# KursSCH2.net
KiCad netlist of a schematic drawn in Altium Designer
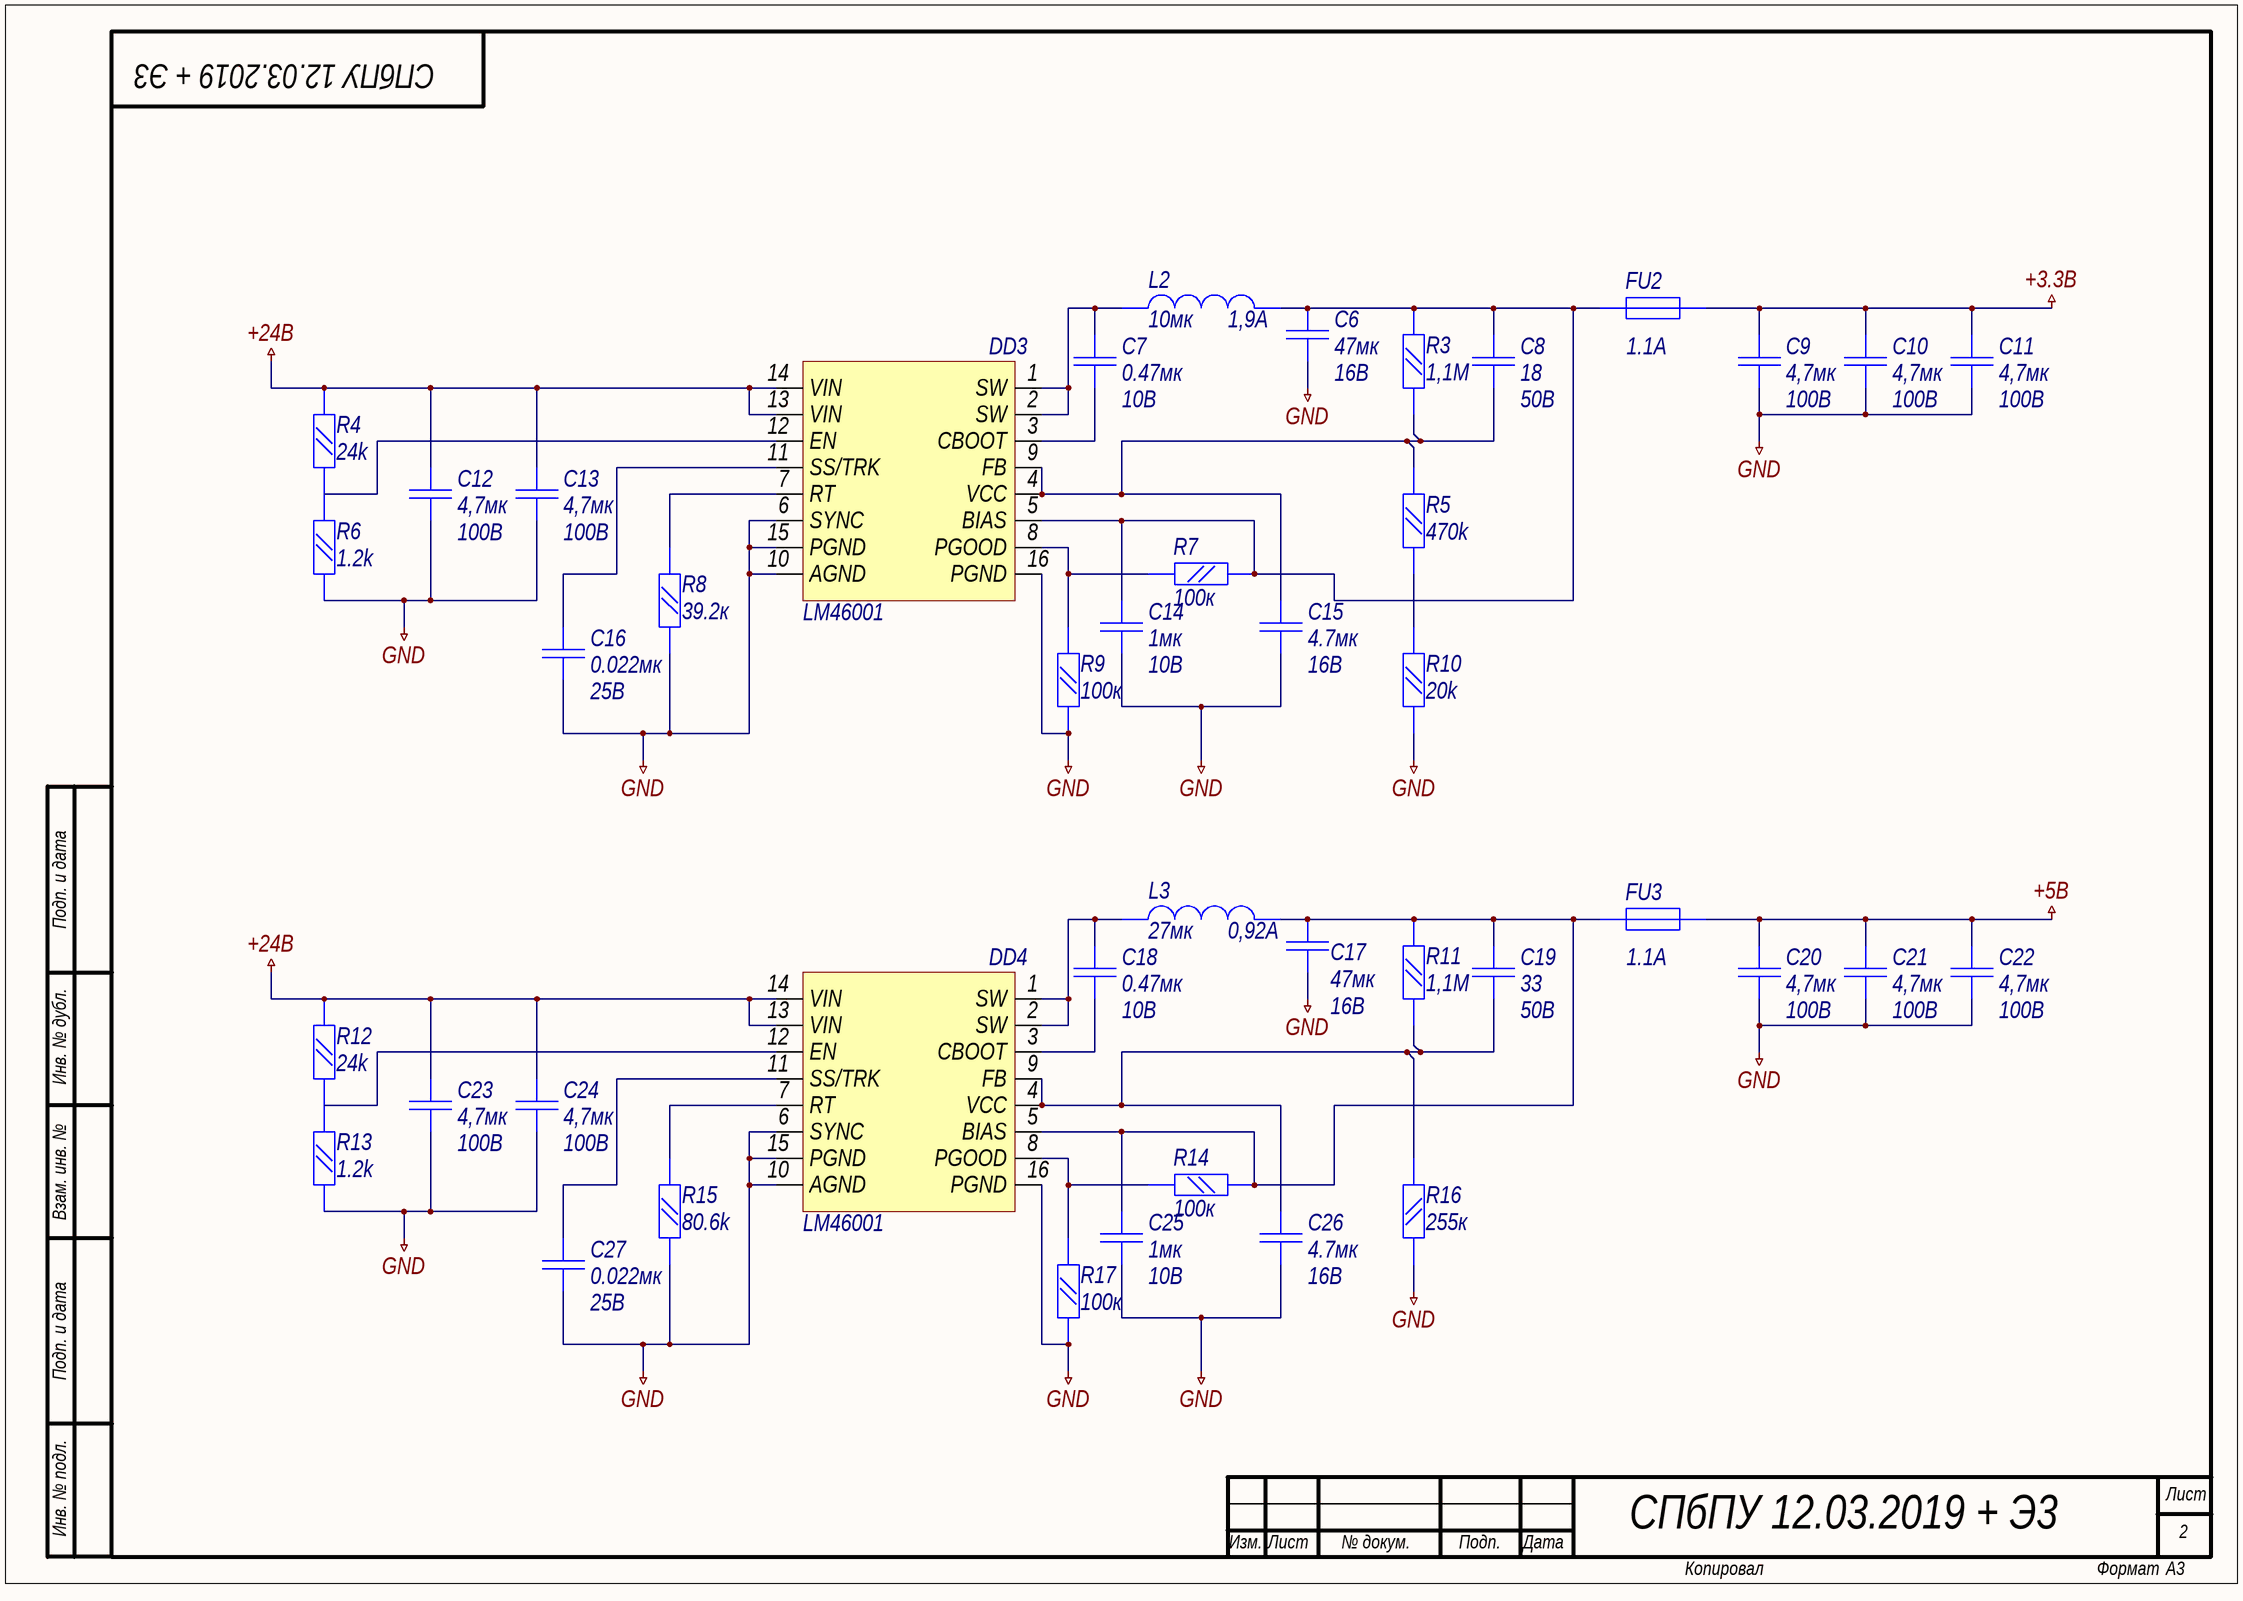
[diagram p0: KursSCH2.schdoc]

(export (version "E")
  (design (tool "Eeschema 10.0.6"))
  (components
    (comp (ref "C6")
      (value "47мк")
      (footprint "C1210")
      (fields
        (field (name "VOLTAGE") "16В")
        (field (name "PART NUMBER") "GRM32ER61C476KE15L")
        (field (name "TOLERANCE") "±10%")
        (field (name "MANUFACTURER") "Murata")
      )
      (libsource (lib "Lib_IMP_GOST") (part "Capacitor"))
    )
    (comp (ref "C7")
      (value "0.47мк")
      (footprint "C0603")
      (fields
        (field (name "VOLTAGE") "10В")
        (field (name "PART NUMBER") "GRM188R71A474KA61D")
        (field (name "TOLERANCE") "±10%")
        (field (name "MANUFACTURER") "Murata")
      )
      (libsource (lib "Lib_IMP_GOST") (part "Capacitor"))
    )
    (comp (ref "C8")
      (value "18")
      (footprint "C0402")
      (fields
        (field (name "VOLTAGE") "50В")
        (field (name "PART NUMBER") "GRM1555C1H180JA01D")
        (field (name "TOLERANCE") "±5%")
        (field (name "MANUFACTURER") "Murata")
      )
      (libsource (lib "Lib_IMP_GOST") (part "Capacitor"))
    )
    (comp (ref "C9")
      (value "4,7мк")
      (footprint "C1206")
      (fields
        (field (name "VOLTAGE") "100В")
        (field (name "PART NUMBER") "GRM31CC72A475ME11")
        (field (name "TOLERANCE") "±10%")
        (field (name "MANUFACTURER") "Murata")
      )
      (libsource (lib "Lib_IMP_GOST") (part "Capacitor"))
    )
    (comp (ref "C10")
      (value "4,7мк")
      (footprint "C1206")
      (fields
        (field (name "VOLTAGE") "100В")
        (field (name "PART NUMBER") "GRM31CC72A475ME11")
        (field (name "TOLERANCE") "±10%")
        (field (name "MANUFACTURER") "Murata")
      )
      (libsource (lib "Lib_IMP_GOST") (part "Capacitor"))
    )
    (comp (ref "C11")
      (value "4,7мк")
      (footprint "C1206")
      (fields
        (field (name "VOLTAGE") "100В")
        (field (name "PART NUMBER") "GRM31CC72A475ME11")
        (field (name "TOLERANCE") "±10%")
        (field (name "MANUFACTURER") "Murata")
      )
      (libsource (lib "Lib_IMP_GOST") (part "Capacitor"))
    )
    (comp (ref "C12")
      (value "4,7мк")
      (footprint "C1206")
      (fields
        (field (name "VOLTAGE") "100В")
        (field (name "PART NUMBER") "GRM31CC72A475ME11")
        (field (name "TOLERANCE") "±10%")
        (field (name "MANUFACTURER") "Murata")
      )
      (libsource (lib "Lib_IMP_GOST") (part "Capacitor"))
    )
    (comp (ref "C13")
      (value "4,7мк")
      (footprint "C1206")
      (fields
        (field (name "VOLTAGE") "100В")
        (field (name "PART NUMBER") "GRM31CC72A475ME11")
        (field (name "TOLERANCE") "±10%")
        (field (name "MANUFACTURER") "Murata")
      )
      (libsource (lib "Lib_IMP_GOST") (part "Capacitor"))
    )
    (comp (ref "C14")
      (value "1мк")
      (footprint "C0603")
      (fields
        (field (name "VOLTAGE") "10В")
        (field (name "PART NUMBER") "GRM188R61A105KA01D")
        (field (name "TOLERANCE") "±10%")
        (field (name "MANUFACTURER") "Murata")
      )
      (libsource (lib "Lib_IMP_GOST") (part "Capacitor"))
    )
    (comp (ref "C15")
      (value "4.7мк")
      (footprint "C0603")
      (fields
        (field (name "VOLTAGE") "16В")
        (field (name "PART NUMBER") "GRM188R61A475KE15D")
        (field (name "TOLERANCE") "±10%")
        (field (name "MANUFACTURER") "Murata")
      )
      (libsource (lib "Lib_IMP_GOST") (part "Capacitor"))
    )
    (comp (ref "C16")
      (value "0.022мк")
      (footprint "C0603")
      (fields
        (field (name "VOLTAGE") "25В")
        (field (name "PART NUMBER") "GRM188R71E223JA01D")
        (field (name "TOLERANCE") "±5%")
        (field (name "MANUFACTURER") "Murata")
      )
      (libsource (lib "Lib_IMP_GOST") (part "Capacitor"))
    )
    (comp (ref "C17")
      (value "47мк")
      (footprint "C1210")
      (fields
        (field (name "VOLTAGE") "16В")
        (field (name "PART NUMBER") "GRM32ER61C476KE15L")
        (field (name "TOLERANCE") "±10%")
        (field (name "MANUFACTURER") "Murata")
      )
      (libsource (lib "Lib_IMP_GOST") (part "Capacitor"))
    )
    (comp (ref "C18")
      (value "0.47мк")
      (footprint "C0603")
      (fields
        (field (name "VOLTAGE") "10В")
        (field (name "PART NUMBER") "GRM188R71A474KA61D")
        (field (name "TOLERANCE") "±10%")
        (field (name "MANUFACTURER") "Murata")
      )
      (libsource (lib "Lib_IMP_GOST") (part "Capacitor"))
    )
    (comp (ref "C19")
      (value "33")
      (footprint "C0402")
      (fields
        (field (name "VOLTAGE") "50В")
        (field (name "PART NUMBER") "GRM1555C1H330JA01D")
        (field (name "TOLERANCE") "±5%")
        (field (name "MANUFACTURER") "Murata")
      )
      (libsource (lib "Lib_IMP_GOST") (part "Capacitor"))
    )
    (comp (ref "C20")
      (value "4,7мк")
      (footprint "C1206")
      (fields
        (field (name "VOLTAGE") "100В")
        (field (name "PART NUMBER") "GRM31CC72A475ME11")
        (field (name "TOLERANCE") "±10%")
        (field (name "MANUFACTURER") "Murata")
      )
      (libsource (lib "Lib_IMP_GOST") (part "Capacitor"))
    )
    (comp (ref "C21")
      (value "4,7мк")
      (footprint "C1206")
      (fields
        (field (name "VOLTAGE") "100В")
        (field (name "PART NUMBER") "GRM31CC72A475ME11")
        (field (name "TOLERANCE") "±10%")
        (field (name "MANUFACTURER") "Murata")
      )
      (libsource (lib "Lib_IMP_GOST") (part "Capacitor"))
    )
    (comp (ref "C22")
      (value "4,7мк")
      (footprint "C1206")
      (fields
        (field (name "VOLTAGE") "100В")
        (field (name "PART NUMBER") "GRM31CC72A475ME11")
        (field (name "TOLERANCE") "±10%")
        (field (name "MANUFACTURER") "Murata")
      )
      (libsource (lib "Lib_IMP_GOST") (part "Capacitor"))
    )
    (comp (ref "C23")
      (value "4,7мк")
      (footprint "C1206")
      (fields
        (field (name "VOLTAGE") "100В")
        (field (name "PART NUMBER") "GRM31CC72A475ME11")
        (field (name "TOLERANCE") "±10%")
        (field (name "MANUFACTURER") "Murata")
      )
      (libsource (lib "Lib_IMP_GOST") (part "Capacitor"))
    )
    (comp (ref "C24")
      (value "4,7мк")
      (footprint "C1206")
      (fields
        (field (name "VOLTAGE") "100В")
        (field (name "PART NUMBER") "GRM31CC72A475ME11")
        (field (name "TOLERANCE") "±10%")
        (field (name "MANUFACTURER") "Murata")
      )
      (libsource (lib "Lib_IMP_GOST") (part "Capacitor"))
    )
    (comp (ref "C25")
      (value "1мк")
      (footprint "C0603")
      (fields
        (field (name "VOLTAGE") "10В")
        (field (name "PART NUMBER") "GRM188R61A105KA01D")
        (field (name "TOLERANCE") "±10%")
        (field (name "MANUFACTURER") "Murata")
      )
      (libsource (lib "Lib_IMP_GOST") (part "Capacitor"))
    )
    (comp (ref "C26")
      (value "4.7мк")
      (footprint "C0603")
      (fields
        (field (name "VOLTAGE") "16В")
        (field (name "PART NUMBER") "GRM188R61A475KE15D")
        (field (name "TOLERANCE") "±10%")
        (field (name "MANUFACTURER") "Murata")
      )
      (libsource (lib "Lib_IMP_GOST") (part "Capacitor"))
    )
    (comp (ref "C27")
      (value "0.022мк")
      (footprint "C0603")
      (fields
        (field (name "VOLTAGE") "25В")
        (field (name "PART NUMBER") "GRM188R71E223JA01D")
        (field (name "TOLERANCE") "±5%")
        (field (name "MANUFACTURER") "Murata")
      )
      (libsource (lib "Lib_IMP_GOST") (part "Capacitor"))
    )
    (comp (ref "DD3") (value "LM46001") (footprint "LM46001") (libsource (lib "Schlib1") (part "LM46001")))
    (comp (ref "DD4") (value "LM46001") (footprint "LM46001") (libsource (lib "Schlib1") (part "LM46001")))
    (comp (ref "FU2")
      (value "Fuse")
      (footprint "F1812")
      (fields (field (name "RATED CURRENT") "1.1A") (field (name "PUBLISHER") "Andrew Danich"))
      (libsource (lib "Lib_IMP_GOST") (part "Fuse"))
    )
    (comp (ref "FU3")
      (value "Fuse")
      (footprint "F1812")
      (fields (field (name "RATED CURRENT") "1.1A") (field (name "PUBLISHER") "Andrew Danich"))
      (libsource (lib "Lib_IMP_GOST") (part "Fuse"))
    )
    (comp (ref "L2")
      (value "7447779115")
      (footprint "747779115")
      (fields (field (name "I") "1,9А") (field (name "L") "10мк"))
      (libsource (lib "Schlib1") (part "7447779115"))
    )
    (comp (ref "L3")
      (value "7447779115")
      (footprint "747779115")
      (fields (field (name "I") "0,92А") (field (name "L") "27мк"))
      (libsource (lib "Schlib1") (part "7447779115"))
    )
    (comp (ref "R3")
      (value "1,1М")
      (footprint "R0805")
      (fields
        (field (name "PART NUMBER") "RC0805JR-071M1L")
        (field (name "TOLERANCE") "±5%")
        (field (name "MANUFACTURER") "Yageo")
      )
      (libsource (lib "Lib_IMP_GOST") (part "Resistor_0,125W"))
    )
    (comp (ref "R4")
      (value "24k")
      (footprint "R0603")
      (fields
        (field (name "PART NUMBER") "RC0603JR-0724KL")
        (field (name "TOLERANCE") "±5%")
        (field (name "MANUFACTURER") "Yageo")
      )
      (libsource (lib "Lib_IMP_GOST") (part "Resistor_0,125W"))
    )
    (comp (ref "R5")
      (value "470k")
      (footprint "R0603")
      (fields
        (field (name "PART NUMBER") "RC0603JR-07470KL")
        (field (name "TOLERANCE") "±5%")
        (field (name "MANUFACTURER") "Yageo")
      )
      (libsource (lib "Lib_IMP_GOST") (part "Resistor_0,125W"))
    )
    (comp (ref "R6")
      (value "1.2k")
      (footprint "R0603")
      (fields
        (field (name "PART NUMBER") "RC0603JR-071K2L")
        (field (name "TOLERANCE") "±5%")
        (field (name "MANUFACTURER") "Yageo")
      )
      (libsource (lib "Lib_IMP_GOST") (part "Resistor_0,125W"))
    )
    (comp (ref "R7")
      (value "100к")
      (footprint "R0805")
      (fields
        (field (name "PART NUMBER") "RC0805JR-07100KL")
        (field (name "TOLERANCE") "±5%")
        (field (name "MANUFACTURER") "Yageo")
      )
      (libsource (lib "Lib_IMP_GOST") (part "Resistor_0,125W"))
    )
    (comp (ref "R8")
      (value "39.2к")
      (footprint "R0603")
      (fields
        (field (name "PART NUMBER") "RC0603FR-0739K2L")
        (field (name "TOLERANCE") "±1%")
        (field (name "MANUFACTURER") "Yageo")
      )
      (libsource (lib "Lib_IMP_GOST") (part "Resistor_0,125W"))
    )
    (comp (ref "R9")
      (value "100к")
      (footprint "R0805")
      (fields
        (field (name "PART NUMBER") "RC0805JR-07100KL")
        (field (name "TOLERANCE") "±5%")
        (field (name "MANUFACTURER") "Yageo")
      )
      (libsource (lib "Lib_IMP_GOST") (part "Resistor_0,125W"))
    )
    (comp (ref "R10")
      (value "20k")
      (footprint "R0603")
      (fields
        (field (name "PART NUMBER") "RC0603FR-0720KL")
        (field (name "TOLERANCE") "±1%")
        (field (name "MANUFACTURER") "Yageo")
      )
      (libsource (lib "Lib_IMP_GOST") (part "Resistor_0,125W"))
    )
    (comp (ref "R11")
      (value "1,1М")
      (footprint "R0805")
      (fields
        (field (name "PART NUMBER") "RC0805JR-071M1L")
        (field (name "TOLERANCE") "±5%")
        (field (name "MANUFACTURER") "Yageo")
      )
      (libsource (lib "Lib_IMP_GOST") (part "Resistor_0,125W"))
    )
    (comp (ref "R12")
      (value "24k")
      (footprint "R0603")
      (fields
        (field (name "PART NUMBER") "RC0603JR-0724KL")
        (field (name "TOLERANCE") "±5%")
        (field (name "MANUFACTURER") "Yageo")
      )
      (libsource (lib "Lib_IMP_GOST") (part "Resistor_0,125W"))
    )
    (comp (ref "R13")
      (value "1.2k")
      (footprint "R0603")
      (fields
        (field (name "PART NUMBER") "RC0603JR-071K2L")
        (field (name "TOLERANCE") "±5%")
        (field (name "MANUFACTURER") "Yageo")
      )
      (libsource (lib "Lib_IMP_GOST") (part "Resistor_0,125W"))
    )
    (comp (ref "R14")
      (value "100к")
      (footprint "R0805")
      (fields
        (field (name "PART NUMBER") "RC0805JR-07100KL")
        (field (name "TOLERANCE") "±5%")
        (field (name "MANUFACTURER") "Yageo")
      )
      (libsource (lib "Lib_IMP_GOST") (part "Resistor_0,125W"))
    )
    (comp (ref "R15")
      (value "80.6k")
      (footprint "R0603")
      (fields
        (field (name "PART NUMBER") "RC0603FR-0780K6L")
        (field (name "TOLERANCE") "±1%")
        (field (name "MANUFACTURER") "Yageo")
      )
      (libsource (lib "Lib_IMP_GOST") (part "Resistor_0,125W"))
    )
    (comp (ref "R16")
      (value "255к")
      (footprint "R0603")
      (fields
        (field (name "PART NUMBER") "RC0603FR-07255KL")
        (field (name "TOLERANCE") "±1%")
        (field (name "MANUFACTURER") "Yageo")
      )
      (libsource (lib "Lib_IMP_GOST") (part "Resistor_0,125W"))
    )
    (comp (ref "R17")
      (value "100к")
      (footprint "R0805")
      (fields
        (field (name "PART NUMBER") "RC0805JR-07100KL")
        (field (name "TOLERANCE") "±5%")
        (field (name "MANUFACTURER") "Yageo")
      )
      (libsource (lib "Lib_IMP_GOST") (part "Resistor_0,125W"))
    )
  )
  (nets
    (net (code "1") (name "+3.3В") (class "Default")
      (node (ref "C10") (pin "2") (pinfunction "2_2") (pintype "passive"))
      (node (ref "C11") (pin "2") (pinfunction "2_2") (pintype "passive"))
      (node (ref "C9") (pin "2") (pinfunction "2_2") (pintype "passive"))
      (node (ref "FU2") (pin "2") (pinfunction "2_2") (pintype "passive"))
    )
    (net (code "2") (name "+5В") (class "Default")
      (node (ref "C20") (pin "2") (pinfunction "2_2") (pintype "passive"))
      (node (ref "C21") (pin "2") (pinfunction "2_2") (pintype "passive"))
      (node (ref "C22") (pin "2") (pinfunction "2_2") (pintype "passive"))
      (node (ref "FU3") (pin "2") (pinfunction "2_2") (pintype "passive"))
    )
    (net (code "3") (name "+24В") (class "Default")
      (node (ref "C12") (pin "2") (pinfunction "2_2") (pintype "passive"))
      (node (ref "C13") (pin "2") (pinfunction "2_2") (pintype "passive"))
      (node (ref "C23") (pin "2") (pinfunction "2_2") (pintype "passive"))
      (node (ref "C24") (pin "2") (pinfunction "2_2") (pintype "passive"))
      (node (ref "DD3") (pin "13") (pinfunction "VIN_13") (pintype "passive"))
      (node (ref "DD3") (pin "14") (pinfunction "VIN_14") (pintype "passive"))
      (node (ref "DD4") (pin "13") (pinfunction "VIN_13") (pintype "passive"))
      (node (ref "DD4") (pin "14") (pinfunction "VIN_14") (pintype "passive"))
      (node (ref "R12") (pin "2") (pinfunction "2_2") (pintype "passive"))
      (node (ref "R4") (pin "2") (pinfunction "2_2") (pintype "passive"))
    )
    (net (code "4") (name "GND") (class "Default")
      (node (ref "C10") (pin "1") (pinfunction "1_1") (pintype "passive"))
      (node (ref "C11") (pin "1") (pinfunction "1_1") (pintype "passive"))
      (node (ref "C12") (pin "1") (pinfunction "1_1") (pintype "passive"))
      (node (ref "C13") (pin "1") (pinfunction "1_1") (pintype "passive"))
      (node (ref "C14") (pin "1") (pinfunction "1_1") (pintype "passive"))
      (node (ref "C15") (pin "1") (pinfunction "1_1") (pintype "passive"))
      (node (ref "C16") (pin "2") (pinfunction "2_2") (pintype "passive"))
      (node (ref "C17") (pin "1") (pinfunction "1_1") (pintype "passive"))
      (node (ref "C20") (pin "1") (pinfunction "1_1") (pintype "passive"))
      (node (ref "C21") (pin "1") (pinfunction "1_1") (pintype "passive"))
      (node (ref "C22") (pin "1") (pinfunction "1_1") (pintype "passive"))
      (node (ref "C23") (pin "1") (pinfunction "1_1") (pintype "passive"))
      (node (ref "C24") (pin "1") (pinfunction "1_1") (pintype "passive"))
      (node (ref "C25") (pin "1") (pinfunction "1_1") (pintype "passive"))
      (node (ref "C26") (pin "1") (pinfunction "1_1") (pintype "passive"))
      (node (ref "C27") (pin "2") (pinfunction "2_2") (pintype "passive"))
      (node (ref "C6") (pin "1") (pinfunction "1_1") (pintype "passive"))
      (node (ref "C9") (pin "1") (pinfunction "1_1") (pintype "passive"))
      (node (ref "DD3") (pin "10") (pinfunction "AGND_10") (pintype "passive"))
      (node (ref "DD3") (pin "15") (pinfunction "PGND_15") (pintype "passive"))
      (node (ref "DD3") (pin "16") (pinfunction "PGND_16") (pintype "passive"))
      (node (ref "DD3") (pin "6") (pinfunction "SYNC_6") (pintype "passive"))
      (node (ref "DD4") (pin "10") (pinfunction "AGND_10") (pintype "passive"))
      (node (ref "DD4") (pin "15") (pinfunction "PGND_15") (pintype "passive"))
      (node (ref "DD4") (pin "16") (pinfunction "PGND_16") (pintype "passive"))
      (node (ref "DD4") (pin "6") (pinfunction "SYNC_6") (pintype "passive"))
      (node (ref "R10") (pin "1") (pinfunction "1_1") (pintype "passive"))
      (node (ref "R13") (pin "1") (pinfunction "1_1") (pintype "passive"))
      (node (ref "R15") (pin "1") (pinfunction "1_1") (pintype "passive"))
      (node (ref "R16") (pin "1") (pinfunction "1_1") (pintype "passive"))
      (node (ref "R17") (pin "1") (pinfunction "1_1") (pintype "passive"))
      (node (ref "R6") (pin "1") (pinfunction "1_1") (pintype "passive"))
      (node (ref "R8") (pin "1") (pinfunction "1_1") (pintype "passive"))
      (node (ref "R9") (pin "1") (pinfunction "1_1") (pintype "passive"))
    )
    (net (code "5") (name "Net-(C7-Pad2)") (class "Default")
      (node (ref "C7") (pin "2") (pinfunction "2_2") (pintype "passive"))
      (node (ref "DD3") (pin "1") (pinfunction "SW_1") (pintype "passive"))
      (node (ref "DD3") (pin "2") (pinfunction "SW_2") (pintype "passive"))
      (node (ref "L2") (pin "1") (pinfunction "1_1") (pintype "passive"))
    )
    (net (code "6") (name "Net-(C18-Pad2)") (class "Default")
      (node (ref "C18") (pin "2") (pinfunction "2_2") (pintype "passive"))
      (node (ref "DD4") (pin "1") (pinfunction "SW_1") (pintype "passive"))
      (node (ref "DD4") (pin "2") (pinfunction "SW_2") (pintype "passive"))
      (node (ref "L3") (pin "1") (pinfunction "1_1") (pintype "passive"))
    )
    (net (code "7") (name "Net-(DD3-BIAS)") (class "Default")
      (node (ref "C14") (pin "2") (pinfunction "2_2") (pintype "passive"))
      (node (ref "C6") (pin "2") (pinfunction "2_2") (pintype "passive"))
      (node (ref "C8") (pin "2") (pinfunction "2_2") (pintype "passive"))
      (node (ref "DD3") (pin "5") (pinfunction "BIAS_5") (pintype "passive"))
      (node (ref "FU2") (pin "1") (pinfunction "1_1") (pintype "passive"))
      (node (ref "L2") (pin "2") (pinfunction "2_2") (pintype "passive"))
      (node (ref "R3") (pin "2") (pinfunction "2_2") (pintype "passive"))
      (node (ref "R7") (pin "1") (pinfunction "1_1") (pintype "passive"))
    )
    (net (code "8") (name "Net-(DD3-CBOOT)") (class "Default")
      (node (ref "C7") (pin "1") (pinfunction "1_1") (pintype "passive"))
      (node (ref "DD3") (pin "3") (pinfunction "CBOOT_3") (pintype "passive"))
    )
    (net (code "9") (name "Net-(DD3-EN)") (class "Default")
      (node (ref "DD3") (pin "12") (pinfunction "EN_12") (pintype "passive"))
      (node (ref "R4") (pin "1") (pinfunction "1_1") (pintype "passive"))
      (node (ref "R6") (pin "2") (pinfunction "2_2") (pintype "passive"))
    )
    (net (code "10") (name "Net-(DD3-FB)") (class "Default")
      (node (ref "C15") (pin "2") (pinfunction "2_2") (pintype "passive"))
      (node (ref "C8") (pin "1") (pinfunction "1_1") (pintype "passive"))
      (node (ref "DD3") (pin "4") (pinfunction "VCC_4") (pintype "passive"))
      (node (ref "DD3") (pin "9") (pinfunction "FB_9") (pintype "passive"))
      (node (ref "R3") (pin "1") (pinfunction "1_1") (pintype "passive"))
      (node (ref "R5") (pin "2") (pinfunction "2_2") (pintype "passive"))
    )
    (net (code "11") (name "Net-(DD3-PGOOD)") (class "Default")
      (node (ref "DD3") (pin "8") (pinfunction "PGOOD_8") (pintype "passive"))
      (node (ref "R7") (pin "2") (pinfunction "2_2") (pintype "passive"))
      (node (ref "R9") (pin "2") (pinfunction "2_2") (pintype "passive"))
    )
    (net (code "12") (name "Net-(DD3-RT)") (class "Default")
      (node (ref "DD3") (pin "7") (pinfunction "RT_7") (pintype "passive"))
      (node (ref "R8") (pin "2") (pinfunction "2_2") (pintype "passive"))
    )
    (net (code "13") (name "Net-(DD3-SS{slash}TRK)") (class "Default")
      (node (ref "C16") (pin "1") (pinfunction "1_1") (pintype "passive"))
      (node (ref "DD3") (pin "11") (pinfunction "SS/TRK_11") (pintype "passive"))
    )
    (net (code "14") (name "Net-(DD4-BIAS)") (class "Default")
      (node (ref "C17") (pin "2") (pinfunction "2_2") (pintype "passive"))
      (node (ref "C19") (pin "2") (pinfunction "2_2") (pintype "passive"))
      (node (ref "C25") (pin "2") (pinfunction "2_2") (pintype "passive"))
      (node (ref "DD4") (pin "5") (pinfunction "BIAS_5") (pintype "passive"))
      (node (ref "FU3") (pin "1") (pinfunction "1_1") (pintype "passive"))
      (node (ref "L3") (pin "2") (pinfunction "2_2") (pintype "passive"))
      (node (ref "R11") (pin "2") (pinfunction "2_2") (pintype "passive"))
      (node (ref "R14") (pin "2") (pinfunction "2_2") (pintype "passive"))
    )
    (net (code "15") (name "Net-(DD4-CBOOT)") (class "Default")
      (node (ref "C18") (pin "1") (pinfunction "1_1") (pintype "passive"))
      (node (ref "DD4") (pin "3") (pinfunction "CBOOT_3") (pintype "passive"))
    )
    (net (code "16") (name "Net-(DD4-EN)") (class "Default")
      (node (ref "DD4") (pin "12") (pinfunction "EN_12") (pintype "passive"))
      (node (ref "R12") (pin "1") (pinfunction "1_1") (pintype "passive"))
      (node (ref "R13") (pin "2") (pinfunction "2_2") (pintype "passive"))
    )
    (net (code "17") (name "Net-(DD4-FB)") (class "Default")
      (node (ref "C19") (pin "1") (pinfunction "1_1") (pintype "passive"))
      (node (ref "C26") (pin "2") (pinfunction "2_2") (pintype "passive"))
      (node (ref "DD4") (pin "4") (pinfunction "VCC_4") (pintype "passive"))
      (node (ref "DD4") (pin "9") (pinfunction "FB_9") (pintype "passive"))
      (node (ref "R11") (pin "1") (pinfunction "1_1") (pintype "passive"))
      (node (ref "R16") (pin "2") (pinfunction "2_2") (pintype "passive"))
    )
    (net (code "18") (name "Net-(DD4-PGOOD)") (class "Default")
      (node (ref "DD4") (pin "8") (pinfunction "PGOOD_8") (pintype "passive"))
      (node (ref "R14") (pin "1") (pinfunction "1_1") (pintype "passive"))
      (node (ref "R17") (pin "2") (pinfunction "2_2") (pintype "passive"))
    )
    (net (code "19") (name "Net-(DD4-RT)") (class "Default")
      (node (ref "DD4") (pin "7") (pinfunction "RT_7") (pintype "passive"))
      (node (ref "R15") (pin "2") (pinfunction "2_2") (pintype "passive"))
    )
    (net (code "20") (name "Net-(DD4-SS{slash}TRK)") (class "Default")
      (node (ref "C27") (pin "1") (pinfunction "1_1") (pintype "passive"))
      (node (ref "DD4") (pin "11") (pinfunction "SS/TRK_11") (pintype "passive"))
    )
    (net (code "21") (name "Net-(R10-Pad2)") (class "Default")
      (node (ref "R10") (pin "2") (pinfunction "2_2") (pintype "passive"))
      (node (ref "R5") (pin "1") (pinfunction "1_1") (pintype "passive"))
    )
  )
)
